# Tiny_Programmer_Level_Shifter.net
KiCad netlist of a schematic drawn in EAGLE
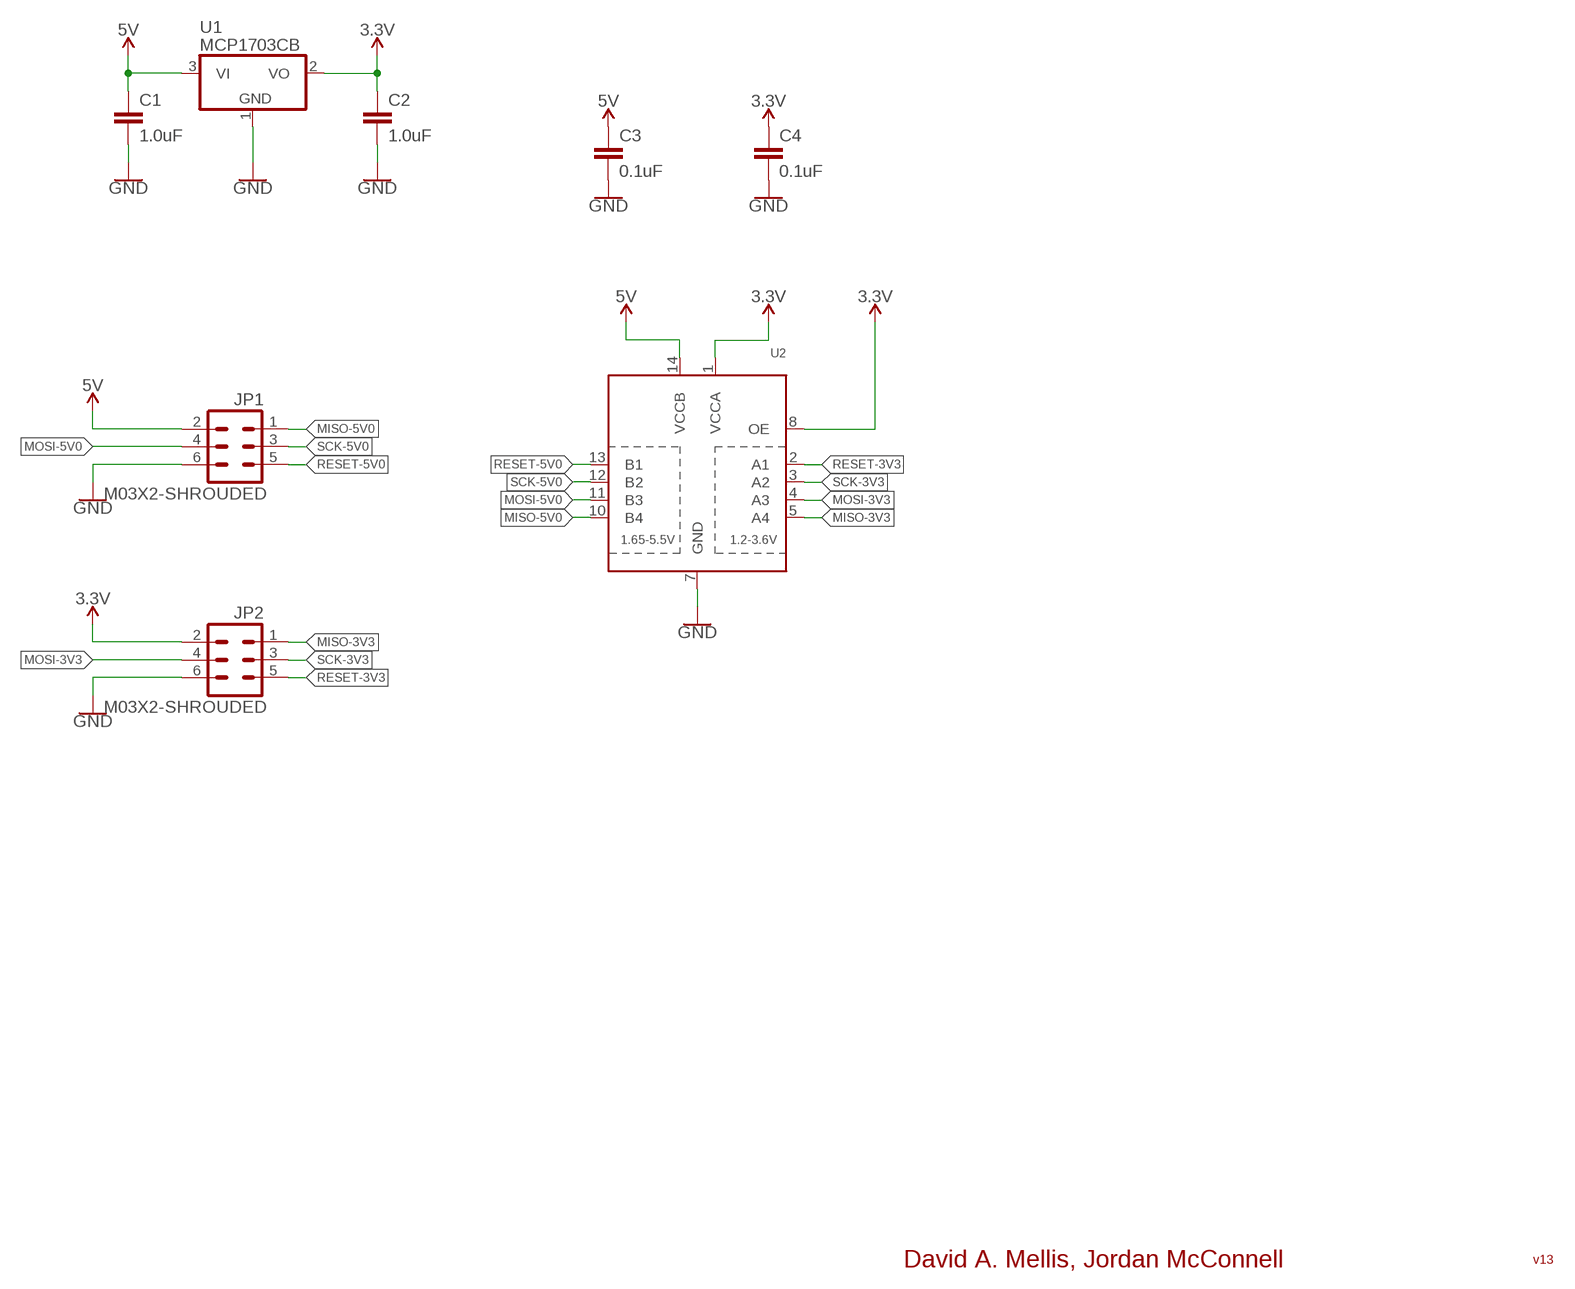
[diagram p0: schematic, sheet 1]

(export (version "E")
  (design (tool "Eeschema 10.0.6"))
  (components
    (comp (ref "C1")
      (value "1.0uF")
      (footprint "eagle-import:0603-CAP")
      (libsource (lib "eagle-import") (part "CAPACITOR-0603"))
    )
    (comp (ref "C2")
      (value "1.0uF")
      (footprint "eagle-import:0603-CAP")
      (libsource (lib "eagle-import") (part "CAPACITOR-0603"))
    )
    (comp (ref "C3")
      (value "0.1uF")
      (footprint "eagle-import:0603-CAP")
      (libsource (lib "eagle-import") (part "CAPACITOR-0603"))
    )
    (comp (ref "C4")
      (value "0.1uF")
      (footprint "eagle-import:0603-CAP")
      (libsource (lib "eagle-import") (part "CAPACITOR-0603"))
    )
    (comp (ref "JP1")
      (value "M03X2-SHROUDED")
      (footprint "eagle-import:2X3-SHROUDED-B")
      (libsource (lib "eagle-import") (part "M03X2-SHROUDED"))
    )
    (comp (ref "JP2")
      (value "M03X2-SHROUDED")
      (footprint "eagle-import:2X3-SHROUDED-B")
      (libsource (lib "eagle-import") (part "M03X2-SHROUDED"))
    )
    (comp (ref "U1")
      (value "MCP1703CB")
      (footprint "eagle-import:SOT23")
      (libsource (lib "eagle-import") (part "MCP1703CB"))
    )
    (comp (ref "U2")
      (value "TXB0104PWR")
      (footprint "eagle-import:TSSOP14")
      (libsource (lib "eagle-import") (part "TXB0104PWR"))
    )
  )
  (nets
    (net (code "1") (name "3.3V") (class "Default")
      (node (ref "C2") (pin "1") (pinfunction "1_1") (pintype "passive"))
      (node (ref "C4") (pin "1") (pinfunction "1_1") (pintype "passive"))
      (node (ref "JP2") (pin "2") (pinfunction "2_2") (pintype "passive"))
      (node (ref "U1") (pin "2") (pinfunction "VO_2") (pintype "passive"))
      (node (ref "U2") (pin "1") (pinfunction "VCCA_1") (pintype "bidirectional"))
      (node (ref "U2") (pin "8") (pinfunction "OE_8") (pintype "bidirectional"))
    )
    (net (code "2") (name "5V") (class "Default")
      (node (ref "C1") (pin "1") (pinfunction "1_1") (pintype "passive"))
      (node (ref "C3") (pin "1") (pinfunction "1_1") (pintype "passive"))
      (node (ref "JP1") (pin "2") (pinfunction "2_2") (pintype "passive"))
      (node (ref "U1") (pin "3") (pinfunction "VI_3") (pintype "input"))
      (node (ref "U2") (pin "14") (pinfunction "VCCB_14") (pintype "bidirectional"))
    )
    (net (code "3") (name "GND") (class "Default")
      (node (ref "C1") (pin "2") (pinfunction "2_2") (pintype "passive"))
      (node (ref "C2") (pin "2") (pinfunction "2_2") (pintype "passive"))
      (node (ref "C3") (pin "2") (pinfunction "2_2") (pintype "passive"))
      (node (ref "C4") (pin "2") (pinfunction "2_2") (pintype "passive"))
      (node (ref "JP1") (pin "6") (pinfunction "6_6") (pintype "passive"))
      (node (ref "JP2") (pin "6") (pinfunction "6_6") (pintype "passive"))
      (node (ref "U1") (pin "1") (pinfunction "GND_1") (pintype "passive"))
      (node (ref "U2") (pin "7") (pinfunction "GND_7") (pintype "bidirectional"))
    )
    (net (code "4") (name "MISO-3V3") (class "Default")
      (node (ref "JP2") (pin "1") (pinfunction "1_1") (pintype "passive"))
      (node (ref "U2") (pin "5") (pinfunction "A4_5") (pintype "bidirectional"))
    )
    (net (code "5") (name "MISO-5V0") (class "Default")
      (node (ref "JP1") (pin "1") (pinfunction "1_1") (pintype "passive"))
      (node (ref "U2") (pin "10") (pinfunction "B4_10") (pintype "bidirectional"))
    )
    (net (code "6") (name "MOSI-3V3") (class "Default")
      (node (ref "JP2") (pin "4") (pinfunction "4_4") (pintype "passive"))
      (node (ref "U2") (pin "4") (pinfunction "A3_4") (pintype "bidirectional"))
    )
    (net (code "7") (name "MOSI-5V0") (class "Default")
      (node (ref "JP1") (pin "4") (pinfunction "4_4") (pintype "passive"))
      (node (ref "U2") (pin "11") (pinfunction "B3_11") (pintype "bidirectional"))
    )
    (net (code "8") (name "RESET-3V3") (class "Default")
      (node (ref "JP2") (pin "5") (pinfunction "5_5") (pintype "passive"))
      (node (ref "U2") (pin "2") (pinfunction "A1_2") (pintype "bidirectional"))
    )
    (net (code "9") (name "RESET-5V0") (class "Default")
      (node (ref "JP1") (pin "5") (pinfunction "5_5") (pintype "passive"))
      (node (ref "U2") (pin "13") (pinfunction "B1_13") (pintype "bidirectional"))
    )
    (net (code "10") (name "SCK-3V3") (class "Default")
      (node (ref "JP2") (pin "3") (pinfunction "3_3") (pintype "passive"))
      (node (ref "U2") (pin "3") (pinfunction "A2_3") (pintype "bidirectional"))
    )
    (net (code "11") (name "SCK-5V0") (class "Default")
      (node (ref "JP1") (pin "3") (pinfunction "3_3") (pintype "passive"))
      (node (ref "U2") (pin "12") (pinfunction "B2_12") (pintype "bidirectional"))
    )
  )
)
